# CON_MEZZANINE_ADC_DAC.net
KiCad netlist of a schematic drawn in Altium Designer
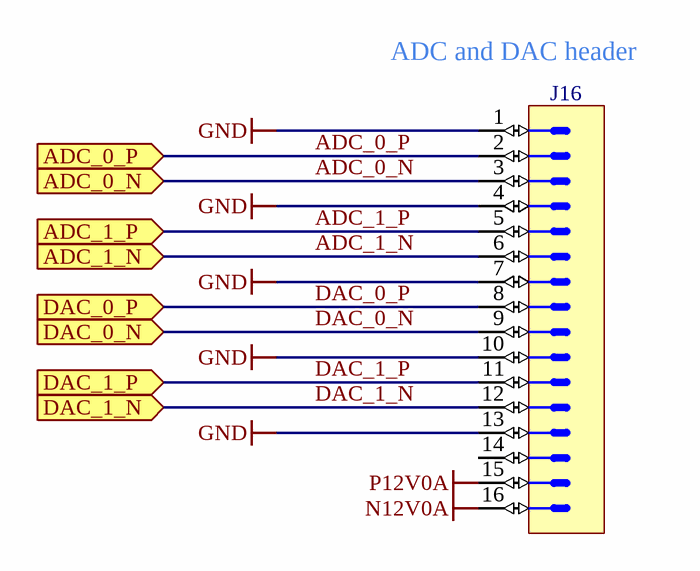
[diagram p0: CON_MEZZANINE_ADC_DAC.SchDoc]

(export (version "E")
  (design (tool "Eeschema 10.0.6"))
  (components
    (comp (ref "J16")
      (value "Header 16")
      (footprint "3M_N2516-6002RB")
      (description "Connector 16 Male")
      (fields
        (field (name "PART NUMBER") "3M_N2516-6002RB")
        (field (name "MANUFACTURER") "3M")
        (field (name "AUTHOR") "CERN DEM JLC")
      )
      (libsource (lib "Connectors") (part "Connector 16 Male"))
    )
  )
  (nets
    (net (code "1") (name "/ADC_0_N") (class "Default")
      (node (ref "J16") (pin "3") (pinfunction "3_3") (pintype "bidirectional"))
    )
    (net (code "2") (name "/ADC_0_P") (class "Default")
      (node (ref "J16") (pin "2") (pinfunction "2_2") (pintype "bidirectional"))
    )
    (net (code "3") (name "/ADC_1_N") (class "Default")
      (node (ref "J16") (pin "6") (pinfunction "6_6") (pintype "bidirectional"))
    )
    (net (code "4") (name "/ADC_1_P") (class "Default")
      (node (ref "J16") (pin "5") (pinfunction "5_5") (pintype "bidirectional"))
    )
    (net (code "5") (name "/DAC_0_N") (class "Default")
      (node (ref "J16") (pin "9") (pinfunction "9_9") (pintype "bidirectional"))
    )
    (net (code "6") (name "/DAC_0_P") (class "Default")
      (node (ref "J16") (pin "8") (pinfunction "8_8") (pintype "bidirectional"))
    )
    (net (code "7") (name "/DAC_1_N") (class "Default")
      (node (ref "J16") (pin "12") (pinfunction "12_12") (pintype "bidirectional"))
    )
    (net (code "8") (name "/DAC_1_P") (class "Default")
      (node (ref "J16") (pin "11") (pinfunction "11_11") (pintype "bidirectional"))
    )
    (net (code "9") (name "GND") (class "Default")
      (node (ref "J16") (pin "1") (pinfunction "1_1") (pintype "bidirectional"))
      (node (ref "J16") (pin "10") (pinfunction "10_10") (pintype "bidirectional"))
      (node (ref "J16") (pin "13") (pinfunction "13_13") (pintype "bidirectional"))
      (node (ref "J16") (pin "4") (pinfunction "4_4") (pintype "bidirectional"))
      (node (ref "J16") (pin "7") (pinfunction "7_7") (pintype "bidirectional"))
    )
    (net (code "10") (name "N12V0A") (class "Default")
      (node (ref "J16") (pin "16") (pinfunction "16_16") (pintype "bidirectional"))
    )
    (net (code "11") (name "P12V0A") (class "Default")
      (node (ref "J16") (pin "15") (pinfunction "15_15") (pintype "bidirectional"))
    )
    (net (code "12") (name "unconnected-(J16-Pad14)") (class "Default")
      (node (ref "J16") (pin "14") (pinfunction "14_14") (pintype "bidirectional"))
    )
  )
)
